# RAY_MCUModule1.net
KiCad netlist of a schematic drawn in EAGLE
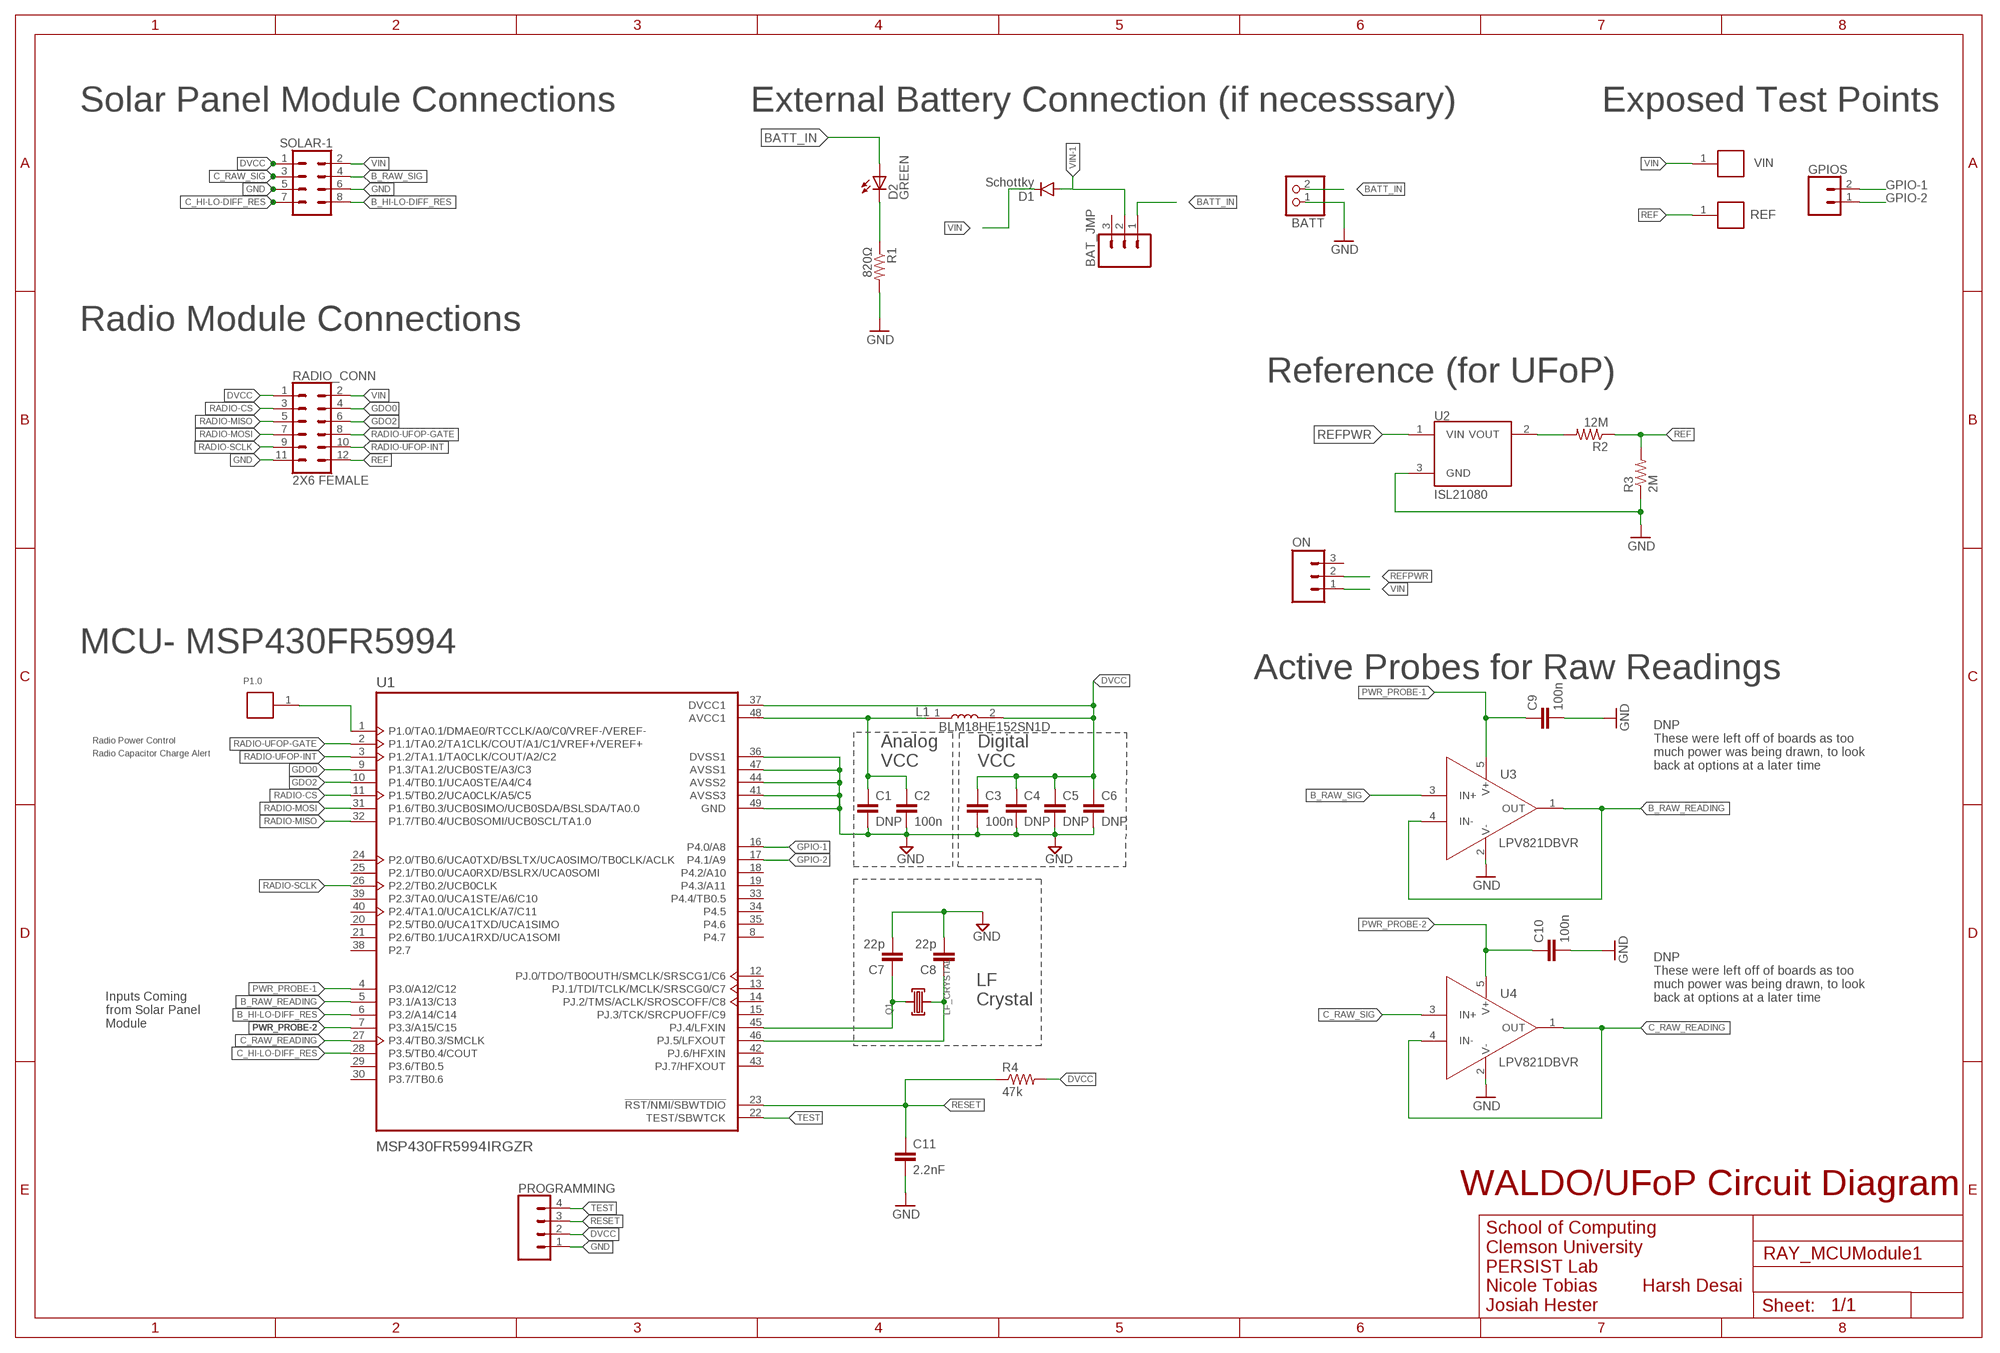
[diagram p0: schematic, sheet 1]

(export (version "E")
  (design (tool "Eeschema 10.0.6"))
  (components
    (comp (ref "BATT")
      (value "PINHD-1X2")
      (footprint "eagle-import:1X02")
      (libsource (lib "eagle-import") (part "PINHD-1X2"))
    )
    (comp (ref "BAT_JMP")
      (value "M03")
      (footprint "eagle-import:1X03-1.27MM")
      (libsource (lib "eagle-import") (part "M03"))
    )
    (comp (ref "C1")
      (value "DNP")
      (footprint "eagle-import:C0603")
      (libsource (lib "eagle-import") (part "C-EUC0603"))
    )
    (comp (ref "C2")
      (value "100n")
      (footprint "eagle-import:C0603")
      (libsource (lib "eagle-import") (part "C-EUC0603"))
    )
    (comp (ref "C3")
      (value "100n")
      (footprint "eagle-import:C0603")
      (libsource (lib "eagle-import") (part "C-EUC0603"))
    )
    (comp (ref "C4")
      (value "DNP")
      (footprint "eagle-import:C0603")
      (libsource (lib "eagle-import") (part "C-EUC0603"))
    )
    (comp (ref "C5")
      (value "DNP")
      (footprint "eagle-import:C0603")
      (libsource (lib "eagle-import") (part "C-EUC0603"))
    )
    (comp (ref "C6")
      (value "DNP")
      (footprint "eagle-import:C0603")
      (libsource (lib "eagle-import") (part "C-EUC0603"))
    )
    (comp (ref "C7")
      (value "22p")
      (footprint "eagle-import:C0603")
      (libsource (lib "eagle-import") (part "C-EUC0603"))
    )
    (comp (ref "C8")
      (value "22p")
      (footprint "eagle-import:C0603")
      (libsource (lib "eagle-import") (part "C-EUC0603"))
    )
    (comp (ref "C9")
      (value "100n")
      (footprint "eagle-import:C0603")
      (libsource (lib "eagle-import") (part "C-EUC0603"))
    )
    (comp (ref "C10")
      (value "100n")
      (footprint "eagle-import:C0603")
      (libsource (lib "eagle-import") (part "C-EUC0603"))
    )
    (comp (ref "C11")
      (value "2.2nF")
      (footprint "eagle-import:C0603")
      (libsource (lib "eagle-import") (part "C-EUC0603"))
    )
    (comp (ref "D1")
      (value "Schottky")
      (footprint "eagle-import:SOD523")
      (libsource (lib "eagle-import") (part "DIODESOD523"))
    )
    (comp (ref "D2")
      (value "GREEN")
      (footprint "eagle-import:CHIP-LED0805")
      (libsource (lib "eagle-import") (part "LEDCHIP-LED0805"))
    )
    (comp (ref "GPIOS")
      (value "CONN_02")
      (footprint "eagle-import:1X02")
      (libsource (lib "eagle-import") (part "CONN_02"))
    )
    (comp (ref "L1")
      (value "BLM18HE152SN1D")
      (footprint "eagle-import:INDC1608X95")
      (fields (field (name "DIGI-KEY_PART_NUMBER") "490-5216-1-ND") (field (name "MF") "Murata"))
      (libsource (lib "eagle-import") (part "BLM18HE152SN1D"))
    )
    (comp (ref "ON")
      (value "M03")
      (footprint "eagle-import:1X03-1.27MM")
      (libsource (lib "eagle-import") (part "M03"))
    )
    (comp (ref "P1.0")
      (value "RCU-0C")
      (footprint "eagle-import:TE_RCU-0C")
      (fields
        (field (name "COMMENT") "RCU-0C _1625854-3_")
        (field (name "MF") "TE Connectivity")
        (field (name "TOLERANCE") "0%")
      )
      (libsource (lib "eagle-import") (part "RCU-0C"))
    )
    (comp (ref "PROGRAMMING")
      (value "CONN_04")
      (footprint "eagle-import:1X04")
      (libsource (lib "eagle-import") (part "CONN_04"))
    )
    (comp (ref "Q1")
      (value "LF_CRYSTAL")
      (footprint "eagle-import:LF_CRYSTAL")
      (libsource (lib "eagle-import") (part "LF_CRYSTAL"))
    )
    (comp (ref "R1")
      (value "820Ω")
      (footprint "eagle-import:0603-RES")
      (libsource (lib "eagle-import") (part "RESISTOR0603"))
    )
    (comp (ref "R2")
      (value "12M")
      (footprint "eagle-import:0603-RES")
      (libsource (lib "eagle-import") (part "RESISTOR0603-RES"))
    )
    (comp (ref "R3")
      (value "2M")
      (footprint "eagle-import:0603-RES")
      (libsource (lib "eagle-import") (part "RESISTOR0603-RES"))
    )
    (comp (ref "R4")
      (value "47k")
      (footprint "eagle-import:0603-RES")
      (libsource (lib "eagle-import") (part "RESISTOR0603-RES"))
    )
    (comp (ref "RADIO_CONN")
      (value "2X6 FEMALE")
      (footprint "eagle-import:2X6")
      (libsource (lib "eagle-import") (part "CONN_06X2PTH_FEMALE"))
    )
    (comp (ref "REF")
      (value "RCU-0C")
      (footprint "eagle-import:TE_RCU-0C")
      (fields
        (field (name "COMMENT") "RCU-0C _1625854-3_")
        (field (name "MF") "TE Connectivity")
        (field (name "TOLERANCE") "0%")
      )
      (libsource (lib "eagle-import") (part "RCU-0C"))
    )
    (comp (ref "SOLAR-1")
      (value "CONN_04X2")
      (footprint "eagle-import:2X4")
      (libsource (lib "eagle-import") (part "CONN_04X2"))
    )
    (comp (ref "U1")
      (value "MSP430FR5994IRGZR")
      (footprint "eagle-import:QFN50P700X700X100-49N")
      (fields (field (name "MF") "Texas Instruments"))
      (libsource (lib "eagle-import") (part "MSP430FR5994IRGZR"))
    )
    (comp (ref "U2")
      (value "ISL21080")
      (footprint "eagle-import:SOT-23")
      (libsource (lib "eagle-import") (part "ISL21080"))
    )
    (comp (ref "U3")
      (value "LPV821DBVR")
      (footprint "eagle-import:SOT95P280X145-5N")
      (fields (field (name "DIGI-KEY_PART_NUMBER") "296-47911-1-ND") (field (name "MF") "Texas Instruments"))
      (libsource (lib "eagle-import") (part "LPV821DBVR"))
    )
    (comp (ref "U4")
      (value "LPV821DBVR")
      (footprint "eagle-import:SOT95P280X145-5N")
      (fields (field (name "DIGI-KEY_PART_NUMBER") "296-47911-1-ND") (field (name "MF") "Texas Instruments"))
      (libsource (lib "eagle-import") (part "LPV821DBVR"))
    )
    (comp (ref "VIN")
      (value "RCU-0C")
      (footprint "eagle-import:TE_RCU-0C")
      (fields
        (field (name "COMMENT") "RCU-0C _1625854-3_")
        (field (name "MF") "TE Connectivity")
        (field (name "TOLERANCE") "0%")
      )
      (libsource (lib "eagle-import") (part "RCU-0C"))
    )
  )
  (nets
    (net (code "1") (name "BATT_IN") (class "Default")
      (node (ref "BATT") (pin "2") (pinfunction "2_2") (pintype "passive"))
      (node (ref "BAT_JMP") (pin "1") (pinfunction "1_1") (pintype "passive"))
      (node (ref "D2") (pin "A") (pinfunction "A_A") (pintype "passive"))
    )
    (net (code "2") (name "B_HI-LO-DIFF_RES") (class "Default")
      (node (ref "SOLAR-1") (pin "8") (pinfunction "8_8") (pintype "passive"))
      (node (ref "U1") (pin "6") (pinfunction "P3.2/A14/C14_6") (pintype "bidirectional"))
    )
    (net (code "3") (name "B_RAW_READING") (class "Default")
      (node (ref "U1") (pin "5") (pinfunction "P3.1/A13/C13_5") (pintype "bidirectional"))
      (node (ref "U3") (pin "1") (pinfunction "OUT_1") (pintype "output"))
      (node (ref "U3") (pin "4") (pinfunction "IN-_4") (pintype "input"))
    )
    (net (code "4") (name "B_RAW_SIG") (class "Default")
      (node (ref "SOLAR-1") (pin "4") (pinfunction "4_4") (pintype "passive"))
      (node (ref "U3") (pin "3") (pinfunction "IN+_3") (pintype "input"))
    )
    (net (code "5") (name "C_HI-LO-DIFF_RES") (class "Default")
      (node (ref "SOLAR-1") (pin "7") (pinfunction "7_7") (pintype "passive"))
      (node (ref "U1") (pin "28") (pinfunction "P3.5/TB0.4/COUT_28") (pintype "bidirectional"))
    )
    (net (code "6") (name "C_RAW_READING") (class "Default")
      (node (ref "U1") (pin "27") (pinfunction "P3.4/TB0.3/SMCLK_27") (pintype "bidirectional"))
      (node (ref "U4") (pin "1") (pinfunction "OUT_1") (pintype "output"))
      (node (ref "U4") (pin "4") (pinfunction "IN-_4") (pintype "input"))
    )
    (net (code "7") (name "C_RAW_SIG") (class "Default")
      (node (ref "SOLAR-1") (pin "3") (pinfunction "3_3") (pintype "passive"))
      (node (ref "U4") (pin "3") (pinfunction "IN+_3") (pintype "input"))
    )
    (net (code "8") (name "DVCC") (class "Default")
      (node (ref "C3") (pin "1") (pinfunction "1_1") (pintype "passive"))
      (node (ref "C4") (pin "1") (pinfunction "1_1") (pintype "passive"))
      (node (ref "C5") (pin "1") (pinfunction "1_1") (pintype "passive"))
      (node (ref "C6") (pin "1") (pinfunction "1_1") (pintype "passive"))
      (node (ref "L1") (pin "2") (pinfunction "2_2") (pintype "passive"))
      (node (ref "PROGRAMMING") (pin "2") (pinfunction "2_2") (pintype "passive"))
      (node (ref "R4") (pin "2") (pinfunction "2_2") (pintype "passive"))
      (node (ref "RADIO_CONN") (pin "1") (pinfunction "1_1") (pintype "passive"))
      (node (ref "SOLAR-1") (pin "1") (pinfunction "1_1") (pintype "passive"))
      (node (ref "U1") (pin "37") (pinfunction "DVCC1_37") (pintype "power_in"))
    )
    (net (code "9") (name "GDO0") (class "Default")
      (node (ref "RADIO_CONN") (pin "4") (pinfunction "4_4") (pintype "passive"))
      (node (ref "U1") (pin "9") (pinfunction "P1.3/TA1.2/UCB0STE/A3/C3_9") (pintype "bidirectional"))
    )
    (net (code "10") (name "GDO2") (class "Default")
      (node (ref "RADIO_CONN") (pin "6") (pinfunction "6_6") (pintype "passive"))
      (node (ref "U1") (pin "10") (pinfunction "P1.4/TB0.1/UCA0STE/A4/C4_10") (pintype "bidirectional"))
    )
    (net (code "11") (name "GND") (class "Default")
      (node (ref "BATT") (pin "1") (pinfunction "1_1") (pintype "passive"))
      (node (ref "C1") (pin "2") (pinfunction "2_2") (pintype "passive"))
      (node (ref "C10") (pin "2") (pinfunction "2_2") (pintype "passive"))
      (node (ref "C11") (pin "2") (pinfunction "2_2") (pintype "passive"))
      (node (ref "C2") (pin "2") (pinfunction "2_2") (pintype "passive"))
      (node (ref "C3") (pin "2") (pinfunction "2_2") (pintype "passive"))
      (node (ref "C4") (pin "2") (pinfunction "2_2") (pintype "passive"))
      (node (ref "C5") (pin "2") (pinfunction "2_2") (pintype "passive"))
      (node (ref "C6") (pin "2") (pinfunction "2_2") (pintype "passive"))
      (node (ref "C7") (pin "2") (pinfunction "2_2") (pintype "passive"))
      (node (ref "C8") (pin "2") (pinfunction "2_2") (pintype "passive"))
      (node (ref "C9") (pin "2") (pinfunction "2_2") (pintype "passive"))
      (node (ref "PROGRAMMING") (pin "1") (pinfunction "1_1") (pintype "passive"))
      (node (ref "R1") (pin "2") (pinfunction "2_2") (pintype "passive"))
      (node (ref "R3") (pin "1") (pinfunction "1_1") (pintype "passive"))
      (node (ref "RADIO_CONN") (pin "11") (pinfunction "11_11") (pintype "passive"))
      (node (ref "SOLAR-1") (pin "5") (pinfunction "5_5") (pintype "passive"))
      (node (ref "SOLAR-1") (pin "6") (pinfunction "6_6") (pintype "passive"))
      (node (ref "U1") (pin "36") (pinfunction "DVSS1_36") (pintype "power_in"))
      (node (ref "U1") (pin "41") (pinfunction "AVSS3_41") (pintype "power_in"))
      (node (ref "U1") (pin "44") (pinfunction "AVSS2_44") (pintype "power_in"))
      (node (ref "U1") (pin "47") (pinfunction "AVSS1_47") (pintype "power_in"))
      (node (ref "U1") (pin "49") (pinfunction "GND_49") (pintype "power_in"))
      (node (ref "U2") (pin "3") (pinfunction "GND_3") (pintype "bidirectional"))
      (node (ref "U3") (pin "2") (pinfunction "V-_2") (pintype "power_in"))
      (node (ref "U4") (pin "2") (pinfunction "V-_2") (pintype "power_in"))
    )
    (net (code "12") (name "GPIO-1") (class "Default")
      (node (ref "GPIOS") (pin "2") (pinfunction "2_2") (pintype "passive"))
      (node (ref "U1") (pin "16") (pinfunction "P4.0/A8_16") (pintype "bidirectional"))
    )
    (net (code "13") (name "GPIO-2") (class "Default")
      (node (ref "GPIOS") (pin "1") (pinfunction "1_1") (pintype "passive"))
      (node (ref "U1") (pin "17") (pinfunction "P4.1/A9_17") (pintype "bidirectional"))
    )
    (net (code "14") (name "Net-(D2-PadC)") (class "Default")
      (node (ref "D2") (pin "C") (pinfunction "C_C") (pintype "passive"))
      (node (ref "R1") (pin "1") (pinfunction "1_1") (pintype "passive"))
    )
    (net (code "15") (name "Net-(U1-AVCC1)") (class "Default")
      (node (ref "C1") (pin "1") (pinfunction "1_1") (pintype "passive"))
      (node (ref "C2") (pin "1") (pinfunction "1_1") (pintype "passive"))
      (node (ref "L1") (pin "1") (pinfunction "1_1") (pintype "passive"))
      (node (ref "U1") (pin "48") (pinfunction "AVCC1_48") (pintype "power_in"))
    )
    (net (code "16") (name "Net-(U1-P1.0{slash}TA0.1{slash}DMAE0{slash}RTCCLK{slash}A0{slash}C0{slash}VREF-{slash}VEREF-)") (class "Default")
      (node (ref "P1.0") (pin "1") (pinfunction "1_1") (pintype "passive"))
      (node (ref "U1") (pin "1") (pinfunction "P1.0/TA0.1/DMAE0/RTCCLK/A0/C0/VREF-/VEREF-_1") (pintype "bidirectional"))
    )
    (net (code "17") (name "Net-(U1-PJ.4{slash}LFXIN)") (class "Default")
      (node (ref "C7") (pin "1") (pinfunction "1_1") (pintype "passive"))
      (node (ref "Q1") (pin "1") (pinfunction "1_1") (pintype "bidirectional"))
      (node (ref "U1") (pin "45") (pinfunction "PJ.4/LFXIN_45") (pintype "bidirectional"))
    )
    (net (code "18") (name "Net-(U1-PJ.5{slash}LFXOUT)") (class "Default")
      (node (ref "C8") (pin "1") (pinfunction "1_1") (pintype "passive"))
      (node (ref "Q1") (pin "2") (pinfunction "2_2") (pintype "bidirectional"))
      (node (ref "U1") (pin "46") (pinfunction "PJ.5/LFXOUT_46") (pintype "bidirectional"))
    )
    (net (code "19") (name "Net-(U2-VOUT)") (class "Default")
      (node (ref "R2") (pin "2") (pinfunction "2_2") (pintype "passive"))
      (node (ref "U2") (pin "2") (pinfunction "VOUT_2") (pintype "bidirectional"))
    )
    (net (code "20") (name "PWR_PROBE-1") (class "Default")
      (node (ref "C9") (pin "1") (pinfunction "1_1") (pintype "passive"))
      (node (ref "U1") (pin "4") (pinfunction "P3.0/A12/C12_4") (pintype "bidirectional"))
      (node (ref "U3") (pin "5") (pinfunction "V+_5") (pintype "power_in"))
    )
    (net (code "21") (name "PWR_PROBE-2") (class "Default")
      (node (ref "C10") (pin "1") (pinfunction "1_1") (pintype "passive"))
      (node (ref "U1") (pin "7") (pinfunction "P3.3/A15/C15_7") (pintype "bidirectional"))
      (node (ref "U4") (pin "5") (pinfunction "V+_5") (pintype "power_in"))
    )
    (net (code "22") (name "RADIO-CS") (class "Default")
      (node (ref "RADIO_CONN") (pin "3") (pinfunction "3_3") (pintype "passive"))
      (node (ref "U1") (pin "11") (pinfunction "P1.5/TB0.2/UCA0CLK/A5/C5_11") (pintype "bidirectional"))
    )
    (net (code "23") (name "RADIO-MISO") (class "Default")
      (node (ref "RADIO_CONN") (pin "5") (pinfunction "5_5") (pintype "passive"))
      (node (ref "U1") (pin "32") (pinfunction "P1.7/TB0.4/UCB0SOMI/UCB0SCL/TA1.0_32") (pintype "bidirectional"))
    )
    (net (code "24") (name "RADIO-MOSI") (class "Default")
      (node (ref "RADIO_CONN") (pin "7") (pinfunction "7_7") (pintype "passive"))
      (node (ref "U1") (pin "31") (pinfunction "P1.6/TB0.3/UCB0SIMO/UCB0SDA/BSLSDA/TA0.0_31") (pintype "bidirectional"))
    )
    (net (code "25") (name "RADIO-SCLK") (class "Default")
      (node (ref "RADIO_CONN") (pin "9") (pinfunction "9_9") (pintype "passive"))
      (node (ref "U1") (pin "26") (pinfunction "P2.2/TB0.2/UCB0CLK_26") (pintype "bidirectional"))
    )
    (net (code "26") (name "RADIO-UFOP-GATE") (class "Default")
      (node (ref "RADIO_CONN") (pin "8") (pinfunction "8_8") (pintype "passive"))
      (node (ref "U1") (pin "2") (pinfunction "P1.1/TA0.2/TA1CLK/COUT/A1/C1/VREF+/VEREF+_2") (pintype "bidirectional"))
    )
    (net (code "27") (name "RADIO-UFOP-INT") (class "Default")
      (node (ref "RADIO_CONN") (pin "10") (pinfunction "10_10") (pintype "passive"))
      (node (ref "U1") (pin "3") (pinfunction "P1.2/TA1.1/TA0CLK/COUT/A2/C2_3") (pintype "bidirectional"))
    )
    (net (code "28") (name "REF") (class "Default")
      (node (ref "R2") (pin "1") (pinfunction "1_1") (pintype "passive"))
      (node (ref "R3") (pin "2") (pinfunction "2_2") (pintype "passive"))
      (node (ref "RADIO_CONN") (pin "12") (pinfunction "12_12") (pintype "passive"))
      (node (ref "REF") (pin "1") (pinfunction "1_1") (pintype "passive"))
    )
    (net (code "29") (name "REFPWR") (class "Default")
      (node (ref "ON") (pin "2") (pinfunction "2_2") (pintype "passive"))
      (node (ref "U2") (pin "1") (pinfunction "VIN_1") (pintype "bidirectional"))
    )
    (net (code "30") (name "RESET") (class "Default")
      (node (ref "C11") (pin "1") (pinfunction "1_1") (pintype "passive"))
      (node (ref "PROGRAMMING") (pin "3") (pinfunction "3_3") (pintype "passive"))
      (node (ref "R4") (pin "1") (pinfunction "1_1") (pintype "passive"))
      (node (ref "U1") (pin "23") (pinfunction "~{RST/NMI/SBWTDIO}_23") (pintype "bidirectional"))
    )
    (net (code "31") (name "TEST") (class "Default")
      (node (ref "PROGRAMMING") (pin "4") (pinfunction "4_4") (pintype "passive"))
      (node (ref "U1") (pin "22") (pinfunction "TEST/SBWTCK_22") (pintype "bidirectional"))
    )
    (net (code "32") (name "VIN") (class "Default")
      (node (ref "D1") (pin "C") (pinfunction "C_C") (pintype "passive"))
      (node (ref "ON") (pin "1") (pinfunction "1_1") (pintype "passive"))
      (node (ref "RADIO_CONN") (pin "2") (pinfunction "2_2") (pintype "passive"))
      (node (ref "SOLAR-1") (pin "2") (pinfunction "2_2") (pintype "passive"))
      (node (ref "VIN") (pin "1") (pinfunction "1_1") (pintype "passive"))
    )
    (net (code "33") (name "VIN-1") (class "Default")
      (node (ref "BAT_JMP") (pin "2") (pinfunction "2_2") (pintype "passive"))
      (node (ref "D1") (pin "A") (pinfunction "A_A") (pintype "passive"))
    )
    (net (code "34") (name "unconnected-(BAT_JMP-Pad3)") (class "Default")
      (node (ref "BAT_JMP") (pin "3") (pinfunction "3_3") (pintype "passive"))
    )
    (net (code "35") (name "unconnected-(ON-Pad3)") (class "Default")
      (node (ref "ON") (pin "3") (pinfunction "3_3") (pintype "passive"))
    )
    (net (code "36") (name "unconnected-(U1-P2.0{slash}TB0.6{slash}UCA0TXD{slash}BSLTX{slash}UCA0SIMO{slash}TB0CLK{slash}ACLK-Pad24)") (class "Default")
      (node (ref "U1") (pin "24") (pinfunction "P2.0/TB0.6/UCA0TXD/BSLTX/UCA0SIMO/TB0CLK/ACLK_24") (pintype "bidirectional"))
    )
    (net (code "37") (name "unconnected-(U1-P2.1{slash}TB0.0{slash}UCA0RXD{slash}BSLRX{slash}UCA0SOMI-Pad25)") (class "Default")
      (node (ref "U1") (pin "25") (pinfunction "P2.1/TB0.0/UCA0RXD/BSLRX/UCA0SOMI_25") (pintype "bidirectional"))
    )
    (net (code "38") (name "unconnected-(U1-P2.3{slash}TA0.0{slash}UCA1STE{slash}A6{slash}C10-Pad39)") (class "Default")
      (node (ref "U1") (pin "39") (pinfunction "P2.3/TA0.0/UCA1STE/A6/C10_39") (pintype "bidirectional"))
    )
    (net (code "39") (name "unconnected-(U1-P2.4{slash}TA1.0{slash}UCA1CLK{slash}A7{slash}C11-Pad40)") (class "Default")
      (node (ref "U1") (pin "40") (pinfunction "P2.4/TA1.0/UCA1CLK/A7/C11_40") (pintype "bidirectional"))
    )
    (net (code "40") (name "unconnected-(U1-P2.5{slash}TB0.0{slash}UCA1TXD{slash}UCA1SIMO-Pad20)") (class "Default")
      (node (ref "U1") (pin "20") (pinfunction "P2.5/TB0.0/UCA1TXD/UCA1SIMO_20") (pintype "bidirectional"))
    )
    (net (code "41") (name "unconnected-(U1-P2.6{slash}TB0.1{slash}UCA1RXD{slash}UCA1SOMI-Pad21)") (class "Default")
      (node (ref "U1") (pin "21") (pinfunction "P2.6/TB0.1/UCA1RXD/UCA1SOMI_21") (pintype "bidirectional"))
    )
    (net (code "42") (name "unconnected-(U1-P2.7-Pad38)") (class "Default")
      (node (ref "U1") (pin "38") (pinfunction "P2.7_38") (pintype "bidirectional"))
    )
    (net (code "43") (name "unconnected-(U1-P3.6{slash}TB0.5-Pad29)") (class "Default")
      (node (ref "U1") (pin "29") (pinfunction "P3.6/TB0.5_29") (pintype "bidirectional"))
    )
    (net (code "44") (name "unconnected-(U1-P3.7{slash}TB0.6-Pad30)") (class "Default")
      (node (ref "U1") (pin "30") (pinfunction "P3.7/TB0.6_30") (pintype "bidirectional"))
    )
    (net (code "45") (name "unconnected-(U1-P4.2{slash}A10-Pad18)") (class "Default")
      (node (ref "U1") (pin "18") (pinfunction "P4.2/A10_18") (pintype "bidirectional"))
    )
    (net (code "46") (name "unconnected-(U1-P4.3{slash}A11-Pad19)") (class "Default")
      (node (ref "U1") (pin "19") (pinfunction "P4.3/A11_19") (pintype "bidirectional"))
    )
    (net (code "47") (name "unconnected-(U1-P4.4{slash}TB0.5-Pad33)") (class "Default")
      (node (ref "U1") (pin "33") (pinfunction "P4.4/TB0.5_33") (pintype "bidirectional"))
    )
    (net (code "48") (name "unconnected-(U1-P4.5-Pad34)") (class "Default")
      (node (ref "U1") (pin "34") (pinfunction "P4.5_34") (pintype "bidirectional"))
    )
    (net (code "49") (name "unconnected-(U1-P4.6-Pad35)") (class "Default")
      (node (ref "U1") (pin "35") (pinfunction "P4.6_35") (pintype "bidirectional"))
    )
    (net (code "50") (name "unconnected-(U1-P4.7-Pad8)") (class "Default")
      (node (ref "U1") (pin "8") (pinfunction "P4.7_8") (pintype "bidirectional"))
    )
    (net (code "51") (name "unconnected-(U1-PJ.0{slash}TDO{slash}TB0OUTH{slash}SMCLK{slash}SRSCG1{slash}C6-Pad12)") (class "Default")
      (node (ref "U1") (pin "12") (pinfunction "PJ.0/TDO/TB0OUTH/SMCLK/SRSCG1/C6_12") (pintype "bidirectional"))
    )
    (net (code "52") (name "unconnected-(U1-PJ.1{slash}TDI{slash}TCLK{slash}MCLK{slash}SRSCG0{slash}C7-Pad13)") (class "Default")
      (node (ref "U1") (pin "13") (pinfunction "PJ.1/TDI/TCLK/MCLK/SRSCG0/C7_13") (pintype "bidirectional"))
    )
    (net (code "53") (name "unconnected-(U1-PJ.2{slash}TMS{slash}ACLK{slash}SROSCOFF{slash}C8-Pad14)") (class "Default")
      (node (ref "U1") (pin "14") (pinfunction "PJ.2/TMS/ACLK/SROSCOFF/C8_14") (pintype "bidirectional"))
    )
    (net (code "54") (name "unconnected-(U1-PJ.3{slash}TCK{slash}SRCPUOFF{slash}C9-Pad15)") (class "Default")
      (node (ref "U1") (pin "15") (pinfunction "PJ.3/TCK/SRCPUOFF/C9_15") (pintype "bidirectional"))
    )
    (net (code "55") (name "unconnected-(U1-PJ.6{slash}HFXIN-Pad42)") (class "Default")
      (node (ref "U1") (pin "42") (pinfunction "PJ.6/HFXIN_42") (pintype "bidirectional"))
    )
    (net (code "56") (name "unconnected-(U1-PJ.7{slash}HFXOUT-Pad43)") (class "Default")
      (node (ref "U1") (pin "43") (pinfunction "PJ.7/HFXOUT_43") (pintype "bidirectional"))
    )
  )
)
